# forno-pcb2.net
KiCad netlist of a schematic drawn in EAGLE
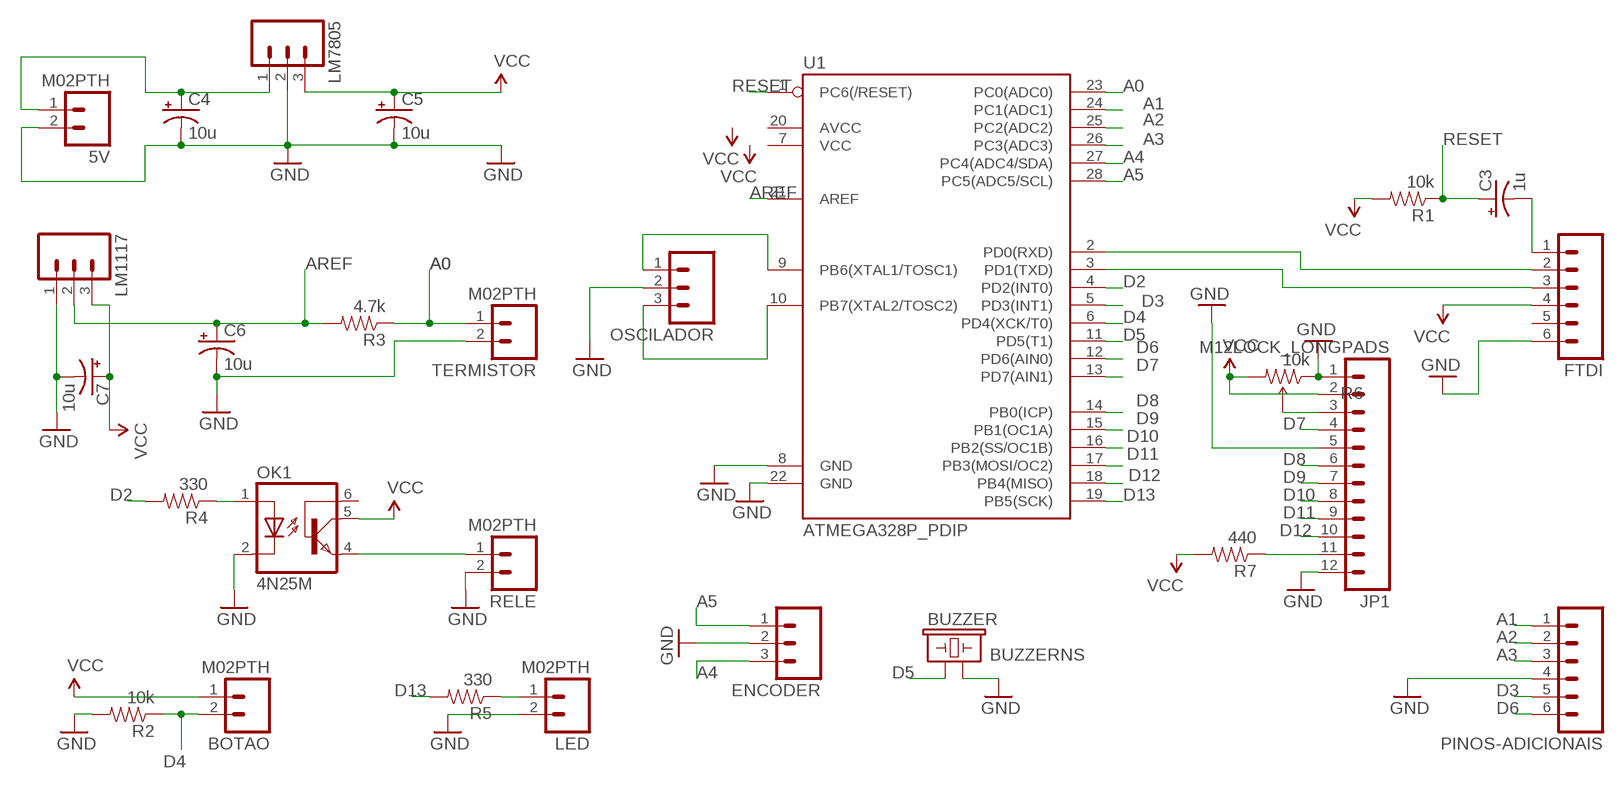
[diagram p0: schematic, sheet 1]

(export (version "E")
  (design (tool "Eeschema 10.0.6"))
  (components
    (comp (ref "5V")
      (value "M02PTH")
      (footprint "eagle-import:1X02")
      (libsource (lib "eagle-import") (part "M02PTH"))
    )
    (comp (ref "BOTAO")
      (value "M02PTH")
      (footprint "eagle-import:1X02")
      (libsource (lib "eagle-import") (part "M02PTH"))
    )
    (comp (ref "BUZZER")
      (value "BUZZERNS")
      (footprint "eagle-import:BUZZER-12MM-NS")
      (libsource (lib "eagle-import") (part "BUZZERNS"))
    )
    (comp (ref "C3")
      (value "1u")
      (footprint "eagle-import:CPOL-RADIAL-10UF-25V")
      (libsource (lib "eagle-import") (part "CAP_POLPTH2"))
    )
    (comp (ref "C4")
      (value "10u")
      (footprint "eagle-import:CPOL-RADIAL-10UF-25V")
      (libsource (lib "eagle-import") (part "CAP_POLPTH2"))
    )
    (comp (ref "C5")
      (value "10u")
      (footprint "eagle-import:CPOL-RADIAL-10UF-25V")
      (libsource (lib "eagle-import") (part "CAP_POLPTH2"))
    )
    (comp (ref "C6")
      (value "10u")
      (footprint "eagle-import:CPOL-RADIAL-10UF-25V")
      (libsource (lib "eagle-import") (part "CAP_POLPTH2"))
    )
    (comp (ref "C7")
      (value "10u")
      (footprint "eagle-import:CPOL-RADIAL-10UF-25V")
      (libsource (lib "eagle-import") (part "CAP_POLPTH2"))
    )
    (comp (ref "ENCODER")
      (value "M03POLAR")
      (footprint "eagle-import:MOLEX-1X3")
      (libsource (lib "eagle-import") (part "M03POLAR"))
    )
    (comp (ref "FTDI")
      (value "M06SIP")
      (footprint "eagle-import:1X06")
      (libsource (lib "eagle-import") (part "M06SIP"))
    )
    (comp (ref "JP1")
      (value "M12LOCK_LONGPADS")
      (footprint "eagle-import:1X12_LOCK_LONGPADS")
      (libsource (lib "eagle-import") (part "M12LOCK_LONGPADS"))
    )
    (comp (ref "LED")
      (value "M02PTH")
      (footprint "eagle-import:1X02")
      (libsource (lib "eagle-import") (part "M02PTH"))
    )
    (comp (ref "LM1117")
      (value "M03POLAR")
      (footprint "eagle-import:MOLEX-1X3")
      (libsource (lib "eagle-import") (part "M03POLAR"))
    )
    (comp (ref "LM7805")
      (value "M03POLAR")
      (footprint "eagle-import:MOLEX-1X3")
      (libsource (lib "eagle-import") (part "M03POLAR"))
    )
    (comp (ref "OK1")
      (value "4N25M")
      (footprint "eagle-import:DIL06")
      (fields (field (name "MPN") "4N25-M"))
      (libsource (lib "eagle-import") (part "4N?M25"))
    )
    (comp (ref "OSCILADOR")
      (value "M03POLAR")
      (footprint "eagle-import:MOLEX-1X3")
      (libsource (lib "eagle-import") (part "M03POLAR"))
    )
    (comp (ref "PINOS-ADICIONAIS")
      (value "M06SIP")
      (footprint "eagle-import:1X06")
      (libsource (lib "eagle-import") (part "M06SIP"))
    )
    (comp (ref "R1")
      (value "10k")
      (footprint "eagle-import:1_6W-RES")
      (libsource (lib "eagle-import") (part "RESISTORPTH-1/6W"))
    )
    (comp (ref "R2")
      (value "10k")
      (footprint "eagle-import:1_6W-RES")
      (libsource (lib "eagle-import") (part "RESISTORPTH-1/6W"))
    )
    (comp (ref "R3")
      (value "4.7k")
      (footprint "eagle-import:1_6W-RES")
      (libsource (lib "eagle-import") (part "RESISTORPTH-1/6W"))
    )
    (comp (ref "R4")
      (value "330")
      (footprint "eagle-import:1_6W-RES")
      (libsource (lib "eagle-import") (part "RESISTORPTH-1/6W"))
    )
    (comp (ref "R5")
      (value "330")
      (footprint "eagle-import:1_6W-RES")
      (libsource (lib "eagle-import") (part "RESISTORPTH-1/6W"))
    )
    (comp (ref "R6")
      (value "10k")
      (footprint "eagle-import:TRIM_POT_PTH")
      (libsource (lib "eagle-import") (part "TRIMPOTPTH"))
    )
    (comp (ref "R7")
      (value "440")
      (footprint "eagle-import:1_6W-RES")
      (libsource (lib "eagle-import") (part "RESISTORPTH-1/6W"))
    )
    (comp (ref "RELE")
      (value "M02PTH")
      (footprint "eagle-import:1X02")
      (libsource (lib "eagle-import") (part "M02PTH"))
    )
    (comp (ref "TERMISTOR")
      (value "M02PTH")
      (footprint "eagle-import:1X02")
      (libsource (lib "eagle-import") (part "M02PTH"))
    )
    (comp (ref "U1")
      (value "ATMEGA328P_PDIP")
      (footprint "eagle-import:DIL28-3")
      (libsource (lib "eagle-import") (part "ATMEGA328P_PDIP"))
    )
  )
  (nets
    (net (code "1") (name "/A0") (class "Default")
      (node (ref "R3") (pin "1") (pinfunction "1_1") (pintype "passive"))
      (node (ref "TERMISTOR") (pin "1") (pinfunction "1_1") (pintype "passive"))
      (node (ref "U1") (pin "23") (pinfunction "PC0(ADC0)_23") (pintype "bidirectional"))
    )
    (net (code "2") (name "/A1") (class "Default")
      (node (ref "PINOS-ADICIONAIS") (pin "1") (pinfunction "1_1") (pintype "passive"))
      (node (ref "U1") (pin "24") (pinfunction "PC1(ADC1)_24") (pintype "bidirectional"))
    )
    (net (code "3") (name "/A2") (class "Default")
      (node (ref "PINOS-ADICIONAIS") (pin "2") (pinfunction "2_2") (pintype "passive"))
      (node (ref "U1") (pin "25") (pinfunction "PC2(ADC2)_25") (pintype "bidirectional"))
    )
    (net (code "4") (name "/A3") (class "Default")
      (node (ref "PINOS-ADICIONAIS") (pin "3") (pinfunction "3_3") (pintype "passive"))
      (node (ref "U1") (pin "26") (pinfunction "PC3(ADC3)_26") (pintype "bidirectional"))
    )
    (net (code "5") (name "/A4") (class "Default")
      (node (ref "ENCODER") (pin "3") (pinfunction "3_3") (pintype "passive"))
      (node (ref "U1") (pin "27") (pinfunction "PC4(ADC4/SDA)_27") (pintype "bidirectional"))
    )
    (net (code "6") (name "/A5") (class "Default")
      (node (ref "ENCODER") (pin "1") (pinfunction "1_1") (pintype "passive"))
      (node (ref "U1") (pin "28") (pinfunction "PC5(ADC5/SCL)_28") (pintype "bidirectional"))
    )
    (net (code "7") (name "/AREF") (class "Default")
      (node (ref "C6") (pin "1") (pinfunction "+_1") (pintype "passive"))
      (node (ref "LM1117") (pin "2") (pinfunction "2_2") (pintype "passive"))
      (node (ref "R3") (pin "2") (pinfunction "2_2") (pintype "passive"))
      (node (ref "U1") (pin "21") (pinfunction "AREF_21") (pintype "bidirectional"))
    )
    (net (code "8") (name "/D2") (class "Default")
      (node (ref "R4") (pin "2") (pinfunction "2_2") (pintype "passive"))
      (node (ref "U1") (pin "4") (pinfunction "PD2(INT0)_4") (pintype "bidirectional"))
    )
    (net (code "9") (name "/D3") (class "Default")
      (node (ref "PINOS-ADICIONAIS") (pin "5") (pinfunction "5_5") (pintype "passive"))
      (node (ref "U1") (pin "5") (pinfunction "PD3(INT1)_5") (pintype "bidirectional"))
    )
    (net (code "10") (name "/D4") (class "Default")
      (node (ref "BOTAO") (pin "2") (pinfunction "2_2") (pintype "passive"))
      (node (ref "R2") (pin "1") (pinfunction "1_1") (pintype "passive"))
      (node (ref "U1") (pin "6") (pinfunction "PD4(XCK/T0)_6") (pintype "bidirectional"))
    )
    (net (code "11") (name "/D5") (class "Default")
      (node (ref "BUZZER") (pin "+") (pinfunction "1_+") (pintype "passive"))
      (node (ref "U1") (pin "11") (pinfunction "PD5(T1)_11") (pintype "bidirectional"))
    )
    (net (code "12") (name "/D6") (class "Default")
      (node (ref "PINOS-ADICIONAIS") (pin "6") (pinfunction "6_6") (pintype "passive"))
      (node (ref "U1") (pin "12") (pinfunction "PD6(AIN0)_12") (pintype "bidirectional"))
    )
    (net (code "13") (name "/D7") (class "Default")
      (node (ref "JP1") (pin "4") (pinfunction "4_4") (pintype "passive"))
      (node (ref "U1") (pin "13") (pinfunction "PD7(AIN1)_13") (pintype "bidirectional"))
    )
    (net (code "14") (name "/D8") (class "Default")
      (node (ref "JP1") (pin "6") (pinfunction "6_6") (pintype "passive"))
      (node (ref "U1") (pin "14") (pinfunction "PB0(ICP)_14") (pintype "bidirectional"))
    )
    (net (code "15") (name "/D9") (class "Default")
      (node (ref "JP1") (pin "7") (pinfunction "7_7") (pintype "passive"))
      (node (ref "U1") (pin "15") (pinfunction "PB1(OC1A)_15") (pintype "bidirectional"))
    )
    (net (code "16") (name "/D10") (class "Default")
      (node (ref "JP1") (pin "8") (pinfunction "8_8") (pintype "passive"))
      (node (ref "U1") (pin "16") (pinfunction "PB2(SS/OC1B)_16") (pintype "bidirectional"))
    )
    (net (code "17") (name "/D11") (class "Default")
      (node (ref "JP1") (pin "9") (pinfunction "9_9") (pintype "passive"))
      (node (ref "U1") (pin "17") (pinfunction "PB3(MOSI/OC2)_17") (pintype "bidirectional"))
    )
    (net (code "18") (name "/D12") (class "Default")
      (node (ref "JP1") (pin "10") (pinfunction "10_10") (pintype "passive"))
      (node (ref "U1") (pin "18") (pinfunction "PB4(MISO)_18") (pintype "bidirectional"))
    )
    (net (code "19") (name "/D13") (class "Default")
      (node (ref "R5") (pin "2") (pinfunction "2_2") (pintype "passive"))
      (node (ref "U1") (pin "19") (pinfunction "PB5(SCK)_19") (pintype "bidirectional"))
    )
    (net (code "20") (name "/RESET") (class "Default")
      (node (ref "C3") (pin "1") (pinfunction "+_1") (pintype "passive"))
      (node (ref "R1") (pin "1") (pinfunction "1_1") (pintype "passive"))
      (node (ref "U1") (pin "1") (pinfunction "PC6(/RESET)_1") (pintype "bidirectional"))
    )
    (net (code "21") (name "GND") (class "Default")
      (node (ref "5V") (pin "2") (pinfunction "2_2") (pintype "passive"))
      (node (ref "BUZZER") (pin "-") (pinfunction "2_-") (pintype "passive"))
      (node (ref "C4") (pin "2") (pinfunction "-_2") (pintype "passive"))
      (node (ref "C5") (pin "2") (pinfunction "-_2") (pintype "passive"))
      (node (ref "C6") (pin "2") (pinfunction "-_2") (pintype "passive"))
      (node (ref "C7") (pin "2") (pinfunction "-_2") (pintype "passive"))
      (node (ref "ENCODER") (pin "2") (pinfunction "2_2") (pintype "passive"))
      (node (ref "FTDI") (pin "6") (pinfunction "6_6") (pintype "passive"))
      (node (ref "JP1") (pin "1") (pinfunction "1_1") (pintype "passive"))
      (node (ref "JP1") (pin "12") (pinfunction "12_12") (pintype "passive"))
      (node (ref "JP1") (pin "5") (pinfunction "5_5") (pintype "passive"))
      (node (ref "LED") (pin "2") (pinfunction "2_2") (pintype "passive"))
      (node (ref "LM1117") (pin "1") (pinfunction "1_1") (pintype "passive"))
      (node (ref "LM7805") (pin "2") (pinfunction "2_2") (pintype "passive"))
      (node (ref "OK1") (pin "2") (pinfunction "C_2") (pintype "passive"))
      (node (ref "OSCILADOR") (pin "2") (pinfunction "2_2") (pintype "passive"))
      (node (ref "PINOS-ADICIONAIS") (pin "4") (pinfunction "4_4") (pintype "passive"))
      (node (ref "R2") (pin "2") (pinfunction "2_2") (pintype "passive"))
      (node (ref "R6") (pin "1") (pinfunction "CCW_1") (pintype "passive"))
      (node (ref "RELE") (pin "2") (pinfunction "2_2") (pintype "passive"))
      (node (ref "TERMISTOR") (pin "2") (pinfunction "2_2") (pintype "passive"))
      (node (ref "U1") (pin "22") (pinfunction "GND_22") (pintype "bidirectional"))
      (node (ref "U1") (pin "8") (pinfunction "GND_8") (pintype "bidirectional"))
    )
    (net (code "22") (name "Net-(C3--)") (class "Default")
      (node (ref "C3") (pin "2") (pinfunction "-_2") (pintype "passive"))
      (node (ref "FTDI") (pin "1") (pinfunction "1_1") (pintype "passive"))
    )
    (net (code "23") (name "Net-(C4-+)") (class "Default")
      (node (ref "5V") (pin "1") (pinfunction "1_1") (pintype "passive"))
      (node (ref "C4") (pin "1") (pinfunction "+_1") (pintype "passive"))
      (node (ref "LM7805") (pin "1") (pinfunction "1_1") (pintype "passive"))
    )
    (net (code "24") (name "Net-(JP1-Pad11)") (class "Default")
      (node (ref "JP1") (pin "11") (pinfunction "11_11") (pintype "passive"))
      (node (ref "R7") (pin "1") (pinfunction "1_1") (pintype "passive"))
    )
    (net (code "25") (name "Net-(LED-Pad1)") (class "Default")
      (node (ref "LED") (pin "1") (pinfunction "1_1") (pintype "passive"))
      (node (ref "R5") (pin "1") (pinfunction "1_1") (pintype "passive"))
    )
    (net (code "26") (name "Net-(OK1-A)") (class "Default")
      (node (ref "OK1") (pin "1") (pinfunction "A_1") (pintype "passive"))
      (node (ref "R4") (pin "1") (pinfunction "1_1") (pintype "passive"))
    )
    (net (code "27") (name "Net-(OK1-EMI)") (class "Default")
      (node (ref "OK1") (pin "4") (pinfunction "EMI_4") (pintype "passive"))
      (node (ref "RELE") (pin "1") (pinfunction "1_1") (pintype "passive"))
    )
    (net (code "28") (name "Net-(R6-WIPER)") (class "Default")
      (node (ref "JP1") (pin "3") (pinfunction "3_3") (pintype "passive"))
      (node (ref "R6") (pin "2") (pinfunction "WIPER_2") (pintype "passive"))
    )
    (net (code "29") (name "Net-(U1-PB6(XTAL1{slash}TOSC1))") (class "Default")
      (node (ref "OSCILADOR") (pin "1") (pinfunction "1_1") (pintype "passive"))
      (node (ref "U1") (pin "9") (pinfunction "PB6(XTAL1/TOSC1)_9") (pintype "bidirectional"))
    )
    (net (code "30") (name "Net-(U1-PB7(XTAL2{slash}TOSC2))") (class "Default")
      (node (ref "OSCILADOR") (pin "3") (pinfunction "3_3") (pintype "passive"))
      (node (ref "U1") (pin "10") (pinfunction "PB7(XTAL2/TOSC2)_10") (pintype "bidirectional"))
    )
    (net (code "31") (name "Net-(U1-PD0(RXD))") (class "Default")
      (node (ref "FTDI") (pin "2") (pinfunction "2_2") (pintype "passive"))
      (node (ref "U1") (pin "2") (pinfunction "PD0(RXD)_2") (pintype "bidirectional"))
    )
    (net (code "32") (name "Net-(U1-PD1(TXD))") (class "Default")
      (node (ref "FTDI") (pin "3") (pinfunction "3_3") (pintype "passive"))
      (node (ref "U1") (pin "3") (pinfunction "PD1(TXD)_3") (pintype "bidirectional"))
    )
    (net (code "33") (name "VCC") (class "Default")
      (node (ref "BOTAO") (pin "1") (pinfunction "1_1") (pintype "passive"))
      (node (ref "C5") (pin "1") (pinfunction "+_1") (pintype "passive"))
      (node (ref "C7") (pin "1") (pinfunction "+_1") (pintype "passive"))
      (node (ref "FTDI") (pin "4") (pinfunction "4_4") (pintype "passive"))
      (node (ref "JP1") (pin "2") (pinfunction "2_2") (pintype "passive"))
      (node (ref "LM1117") (pin "3") (pinfunction "3_3") (pintype "passive"))
      (node (ref "LM7805") (pin "3") (pinfunction "3_3") (pintype "passive"))
      (node (ref "OK1") (pin "5") (pinfunction "COL_5") (pintype "passive"))
      (node (ref "R1") (pin "2") (pinfunction "2_2") (pintype "passive"))
      (node (ref "R6") (pin "3") (pinfunction "CW_3") (pintype "passive"))
      (node (ref "R7") (pin "2") (pinfunction "2_2") (pintype "passive"))
    )
    (net (code "34") (name "unconnected-(FTDI-Pad5)") (class "Default")
      (node (ref "FTDI") (pin "5") (pinfunction "5_5") (pintype "passive"))
    )
    (net (code "35") (name "unconnected-(OK1-BAS-Pad6)") (class "Default")
      (node (ref "OK1") (pin "6") (pinfunction "BAS_6") (pintype "passive"))
    )
    (net (code "36") (name "unconnected-(U1-AVCC-Pad20)") (class "Default")
      (node (ref "U1") (pin "20") (pinfunction "AVCC_20") (pintype "bidirectional"))
    )
    (net (code "37") (name "unconnected-(U1-VCC-Pad7)") (class "Default")
      (node (ref "U1") (pin "7") (pinfunction "VCC_7") (pintype "bidirectional"))
    )
  )
)
